# simple.net
KiCad netlist of a schematic drawn in EAGLE
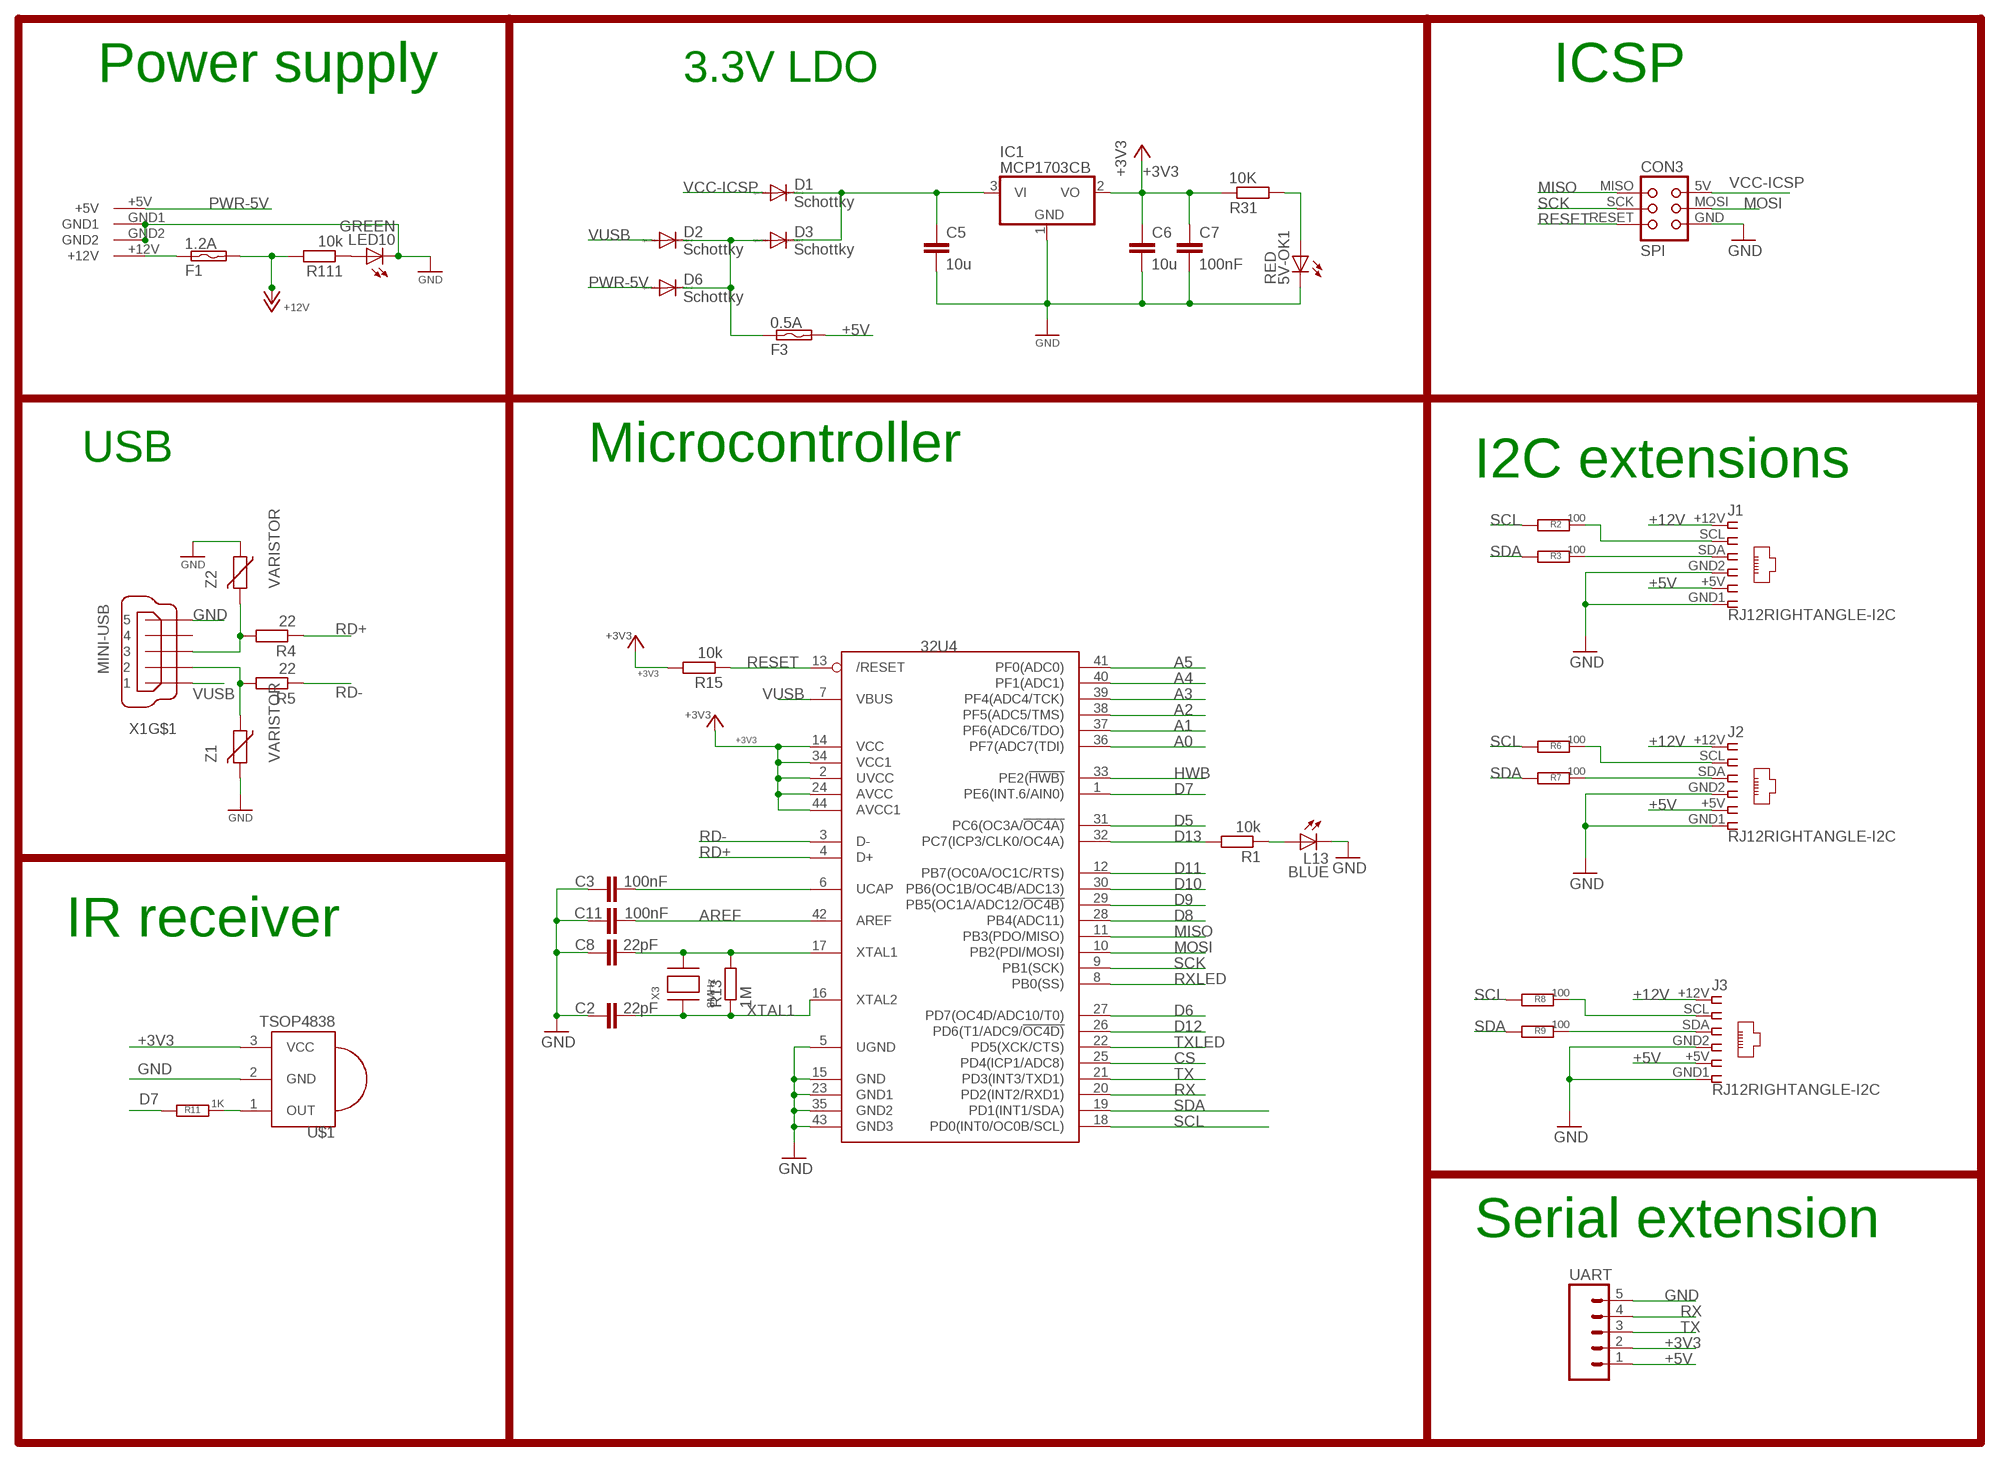
[diagram p0: schematic, sheet 1]

(export (version "E")
  (design (tool "Eeschema 10.0.6"))
  (components
    (comp (ref "5V-OK1")
      (value "RED")
      (footprint "eagle-import:CHIP-LED0805")
      (libsource (lib "eagle-import") (part "LEDCHIP-LED0805"))
    )
    (comp (ref "C2")
      (value "22pF")
      (footprint "eagle-import:C0805K")
      (libsource (lib "eagle-import") (part "C-EUC0805K"))
    )
    (comp (ref "C3")
      (value "100nF")
      (footprint "eagle-import:C0805K")
      (libsource (lib "eagle-import") (part "C-EUC0805K"))
    )
    (comp (ref "C5")
      (value "10u")
      (footprint "eagle-import:C0805K")
      (fields (field (name "MPN") "77-VJ1206V106ZXQTBC"))
      (libsource (lib "eagle-import") (part "rcl_334_C-EUC0805K"))
    )
    (comp (ref "C6")
      (value "10u")
      (footprint "eagle-import:C0805K")
      (fields (field (name "MPN") "77-VJ1206V106ZXQTBC"))
      (libsource (lib "eagle-import") (part "rcl_334_C-EUC0805K"))
    )
    (comp (ref "C7")
      (value "100nF")
      (footprint "eagle-import:C0805K")
      (fields (field (name "MPN") "80-C1206C104K5R"))
      (libsource (lib "eagle-import") (part "rcl_334_C-EUC0805K"))
    )
    (comp (ref "C8")
      (value "22pF")
      (footprint "eagle-import:C0805K")
      (libsource (lib "eagle-import") (part "C-EUC0805K"))
    )
    (comp (ref "C11")
      (value "100nF")
      (footprint "eagle-import:C0805K")
      (libsource (lib "eagle-import") (part "C-EUC0805K"))
    )
    (comp (ref "CON3")
      (value "SPI")
      (footprint "eagle-import:TC2030-MCP-NL")
      (libsource (lib "eagle-import") (part "TINYISPT"))
    )
    (comp (ref "D1")
      (value "Schottky")
      (footprint "eagle-import:SOD123")
      (fields (field (name "MPN") "621-1N5819HW-F"))
      (libsource (lib "eagle-import") (part "MBR0520LT"))
    )
    (comp (ref "D2")
      (value "Schottky")
      (footprint "eagle-import:SOD123")
      (fields (field (name "MPN") "621-1N5819HW-F"))
      (libsource (lib "eagle-import") (part "MBR0520LT"))
    )
    (comp (ref "D3")
      (value "Schottky")
      (footprint "eagle-import:SOD123")
      (fields (field (name "MPN") "621-1N5819HW-F"))
      (libsource (lib "eagle-import") (part "MBR0520LT"))
    )
    (comp (ref "D6")
      (value "Schottky")
      (footprint "eagle-import:SOD123")
      (fields (field (name "MPN") "621-1N5819HW-F"))
      (libsource (lib "eagle-import") (part "MBR0520LT"))
    )
    (comp (ref "F1")
      (value "1.2A")
      (footprint "eagle-import:C1812")
      (libsource (lib "eagle-import") (part "POLYSWITCHSMD1812"))
    )
    (comp (ref "F3")
      (value "0.5A")
      (footprint "eagle-import:C1812")
      (libsource (lib "eagle-import") (part "POLYSWITCHSMD1812"))
    )
    (comp (ref "IC1")
      (value "MCP1703CB")
      (footprint "eagle-import:SOT23")
      (libsource (lib "eagle-import") (part "MCP1703CB"))
    )
    (comp (ref "J1")
      (value "RJ12RIGHTANGLE-I2C")
      (footprint "eagle-import:RJ12-RIGHTANGLE-I2C")
      (libsource (lib "eagle-import") (part "RJ12RIGHTANGLE-I2C"))
    )
    (comp (ref "J2")
      (value "RJ12RIGHTANGLE-I2C")
      (footprint "eagle-import:RJ12-RIGHTANGLE-I2C")
      (libsource (lib "eagle-import") (part "RJ12RIGHTANGLE-I2C"))
    )
    (comp (ref "J3")
      (value "RJ12RIGHTANGLE-I2C")
      (footprint "eagle-import:RJ12-RIGHTANGLE-I2C")
      (libsource (lib "eagle-import") (part "RJ12RIGHTANGLE-I2C"))
    )
    (comp (ref "L13")
      (value "BLUE")
      (footprint "eagle-import:CHIP-LED0805")
      (libsource (lib "eagle-import") (part "LEDCHIP-LED0805"))
    )
    (comp (ref "LED10")
      (value "GREEN")
      (footprint "eagle-import:CHIP-LED0805")
      (libsource (lib "eagle-import") (part "LEDCHIP-LED0805"))
    )
    (comp (ref "R1")
      (value "10k")
      (footprint "eagle-import:M0805")
      (libsource (lib "eagle-import") (part "resistor_348_R-EU_M0805"))
    )
    (comp (ref "R2")
      (value "100")
      (footprint "eagle-import:R0805")
      (libsource (lib "eagle-import") (part "resistor_348_R-EU_R0805"))
    )
    (comp (ref "R3")
      (value "100")
      (footprint "eagle-import:R0805")
      (libsource (lib "eagle-import") (part "resistor_348_R-EU_R0805"))
    )
    (comp (ref "R4")
      (value "22")
      (footprint "eagle-import:R0805")
      (libsource (lib "eagle-import") (part "R-EU_R0805"))
    )
    (comp (ref "R5")
      (value "22")
      (footprint "eagle-import:R0805")
      (libsource (lib "eagle-import") (part "rcl_334_R-EU_R0805"))
    )
    (comp (ref "R6")
      (value "100")
      (footprint "eagle-import:R0805")
      (libsource (lib "eagle-import") (part "resistor_348_R-EU_R0805"))
    )
    (comp (ref "R7")
      (value "100")
      (footprint "eagle-import:R0805")
      (libsource (lib "eagle-import") (part "resistor_348_R-EU_R0805"))
    )
    (comp (ref "R8")
      (value "100")
      (footprint "eagle-import:R0805")
      (libsource (lib "eagle-import") (part "resistor_348_R-EU_R0805"))
    )
    (comp (ref "R9")
      (value "100")
      (footprint "eagle-import:R0805")
      (libsource (lib "eagle-import") (part "resistor_348_R-EU_R0805"))
    )
    (comp (ref "R11")
      (value "1K")
      (footprint "eagle-import:R0805")
      (libsource (lib "eagle-import") (part "resistor_348_R-EU_R0805"))
    )
    (comp (ref "R13")
      (value "1M")
      (footprint "eagle-import:M0805")
      (libsource (lib "eagle-import") (part "R-EU_M0805"))
    )
    (comp (ref "R15")
      (value "10k")
      (footprint "eagle-import:M0805")
      (libsource (lib "eagle-import") (part "resistor_348_R-EU_M0805"))
    )
    (comp (ref "R31")
      (value "10K")
      (footprint "eagle-import:R0805")
      (libsource (lib "eagle-import") (part "resistor_348_R-EU_R0805"))
    )
    (comp (ref "R111")
      (value "10k")
      (footprint "eagle-import:R0805")
      (libsource (lib "eagle-import") (part "R-EU_R0805"))
    )
    (comp (ref "U$1")
      (value "TSOP4838")
      (footprint "eagle-import:PNA460XM")
      (libsource (lib "eagle-import") (part "PNA460XM"))
    )
    (comp (ref "U$4")
      (value "32U4")
      (footprint "eagle-import:TQFP44")
      (libsource (lib "eagle-import") (part "ATMEGA32U4-AU"))
    )
    (comp (ref "U$6")
      (value "KPJX-4S-S")
      (footprint "eagle-import:KPJX-4S-S")
      (libsource (lib "eagle-import") (part "KPJX-4S-S"))
    )
    (comp (ref "UART")
      (value "M05PTH")
      (footprint "eagle-import:1X05")
      (libsource (lib "eagle-import") (part "M05PTH"))
    )
    (comp (ref "X1")
      (value "MINI-USB")
      (footprint "eagle-import:32005-201")
      (fields (field (name "MPN") "649-10033526-N3212LF"))
      (libsource (lib "eagle-import") (part "MINI-USB-SCHIELD-32005-201"))
    )
    (comp (ref "X3")
      (value "8MHz")
      (footprint "eagle-import:NX6035")
      (libsource (lib "eagle-import") (part "XTALNX6035"))
    )
    (comp (ref "Z1")
      (value "VARISTOR")
      (footprint "eagle-import:CT_CN0603")
      (libsource (lib "eagle-import") (part "VARISTORCN0603"))
    )
    (comp (ref "Z2")
      (value "VARISTOR")
      (footprint "eagle-import:CT_CN0603")
      (libsource (lib "eagle-import") (part "VARISTORCN0603"))
    )
  )
  (nets
    (net (code "1") (name "+3V3") (class "Default")
      (node (ref "C6") (pin "1") (pinfunction "1_1") (pintype "passive"))
      (node (ref "C7") (pin "1") (pinfunction "1_1") (pintype "passive"))
      (node (ref "IC1") (pin "2") (pinfunction "VO_2") (pintype "passive"))
      (node (ref "R15") (pin "2") (pinfunction "2_2") (pintype "passive"))
      (node (ref "R31") (pin "1") (pinfunction "1_1") (pintype "passive"))
      (node (ref "U$1") (pin "3") (pinfunction "VCC_3") (pintype "power_in"))
      (node (ref "U$4") (pin "14") (pinfunction "VCC_14") (pintype "bidirectional"))
      (node (ref "U$4") (pin "2") (pinfunction "UVCC_2") (pintype "bidirectional"))
      (node (ref "U$4") (pin "24") (pinfunction "AVCC_24") (pintype "bidirectional"))
      (node (ref "U$4") (pin "34") (pinfunction "VCC1_34") (pintype "bidirectional"))
      (node (ref "U$4") (pin "44") (pinfunction "AVCC1_44") (pintype "bidirectional"))
      (node (ref "UART") (pin "2") (pinfunction "2_2") (pintype "passive"))
    )
    (net (code "2") (name "+12V") (class "Default")
      (node (ref "F1") (pin "2") (pinfunction "2_2") (pintype "passive"))
      (node (ref "J1") (pin "+12V") (pinfunction "1_+12V") (pintype "bidirectional"))
      (node (ref "J2") (pin "+12V") (pinfunction "1_+12V") (pintype "bidirectional"))
      (node (ref "J3") (pin "+12V") (pinfunction "1_+12V") (pintype "bidirectional"))
      (node (ref "R111") (pin "2") (pinfunction "2_2") (pintype "passive"))
    )
    (net (code "3") (name "/+5V") (class "Default")
      (node (ref "F3") (pin "2") (pinfunction "2_2") (pintype "passive"))
      (node (ref "J1") (pin "+5V") (pinfunction "5_+5V") (pintype "bidirectional"))
      (node (ref "J2") (pin "+5V") (pinfunction "5_+5V") (pintype "bidirectional"))
      (node (ref "J3") (pin "+5V") (pinfunction "5_+5V") (pintype "bidirectional"))
      (node (ref "UART") (pin "1") (pinfunction "1_1") (pintype "passive"))
    )
    (net (code "4") (name "/A0") (class "Default")
      (node (ref "U$4") (pin "36") (pinfunction "PF7(ADC7(TDI)_36") (pintype "bidirectional"))
    )
    (net (code "5") (name "/A1") (class "Default")
      (node (ref "U$4") (pin "37") (pinfunction "PF6(ADC6/TDO)_37") (pintype "bidirectional"))
    )
    (net (code "6") (name "/A2") (class "Default")
      (node (ref "U$4") (pin "38") (pinfunction "PF5(ADC5/TMS)_38") (pintype "bidirectional"))
    )
    (net (code "7") (name "/A3") (class "Default")
      (node (ref "U$4") (pin "39") (pinfunction "PF4(ADC4/TCK)_39") (pintype "bidirectional"))
    )
    (net (code "8") (name "/A4") (class "Default")
      (node (ref "U$4") (pin "40") (pinfunction "PF1(ADC1)_40") (pintype "bidirectional"))
    )
    (net (code "9") (name "/A5") (class "Default")
      (node (ref "U$4") (pin "41") (pinfunction "PF0(ADC0)_41") (pintype "bidirectional"))
    )
    (net (code "10") (name "/AREF") (class "Default")
      (node (ref "C11") (pin "1") (pinfunction "1_1") (pintype "passive"))
      (node (ref "U$4") (pin "42") (pinfunction "AREF_42") (pintype "bidirectional"))
    )
    (net (code "11") (name "/CS") (class "Default")
      (node (ref "U$4") (pin "25") (pinfunction "PD4(ICP1/ADC8)_25") (pintype "bidirectional"))
    )
    (net (code "12") (name "/D5") (class "Default")
      (node (ref "U$4") (pin "31") (pinfunction "PC6(OC3A/~{OC4A})_31") (pintype "bidirectional"))
    )
    (net (code "13") (name "/D6") (class "Default")
      (node (ref "U$4") (pin "27") (pinfunction "PD7(OC4D/ADC10/T0)_27") (pintype "bidirectional"))
    )
    (net (code "14") (name "/D7") (class "Default")
      (node (ref "R11") (pin "2") (pinfunction "2_2") (pintype "passive"))
      (node (ref "U$4") (pin "1") (pinfunction "PE6(INT.6/AIN0)_1") (pintype "bidirectional"))
    )
    (net (code "15") (name "/D8") (class "Default")
      (node (ref "U$4") (pin "28") (pinfunction "PB4(ADC11)_28") (pintype "bidirectional"))
    )
    (net (code "16") (name "/D9") (class "Default")
      (node (ref "U$4") (pin "29") (pinfunction "PB5(OC1A/ADC12/~{OC4B})_29") (pintype "bidirectional"))
    )
    (net (code "17") (name "/D10") (class "Default")
      (node (ref "U$4") (pin "30") (pinfunction "PB6(OC1B/OC4B/ADC13)_30") (pintype "bidirectional"))
    )
    (net (code "18") (name "/D11") (class "Default")
      (node (ref "U$4") (pin "12") (pinfunction "PB7(OC0A/OC1C/RTS)_12") (pintype "bidirectional"))
    )
    (net (code "19") (name "/D12") (class "Default")
      (node (ref "U$4") (pin "26") (pinfunction "PD6(T1/ADC9/~{OC4D})_26") (pintype "bidirectional"))
    )
    (net (code "20") (name "/D13") (class "Default")
      (node (ref "R1") (pin "2") (pinfunction "2_2") (pintype "passive"))
      (node (ref "U$4") (pin "32") (pinfunction "PC7(ICP3/CLK0/OC4A)_32") (pintype "bidirectional"))
    )
    (net (code "21") (name "/HWB") (class "Default")
      (node (ref "U$4") (pin "33") (pinfunction "PE2(~{HWB})_33") (pintype "bidirectional"))
    )
    (net (code "22") (name "/MISO") (class "Default")
      (node (ref "CON3") (pin "MISO") (pinfunction "MISO_MISO") (pintype "passive"))
      (node (ref "U$4") (pin "11") (pinfunction "PB3(PDO/MISO)_11") (pintype "bidirectional"))
    )
    (net (code "23") (name "/MOSI") (class "Default")
      (node (ref "CON3") (pin "MOSI") (pinfunction "MOSI_MOSI") (pintype "passive"))
      (node (ref "U$4") (pin "10") (pinfunction "PB2(PDI/MOSI)_10") (pintype "bidirectional"))
    )
    (net (code "24") (name "/PWR-5V") (class "Default")
      (node (ref "D6") (pin "A") (pinfunction "A_A") (pintype "passive"))
      (node (ref "U$6") (pin "+5V") (pinfunction "+5V_+5V") (pintype "power_in"))
    )
    (net (code "25") (name "/RD+") (class "Default")
      (node (ref "R4") (pin "1") (pinfunction "1_1") (pintype "passive"))
      (node (ref "U$4") (pin "4") (pinfunction "D+_4") (pintype "bidirectional"))
    )
    (net (code "26") (name "/RD-") (class "Default")
      (node (ref "R5") (pin "1") (pinfunction "1_1") (pintype "passive"))
      (node (ref "U$4") (pin "3") (pinfunction "D-_3") (pintype "bidirectional"))
    )
    (net (code "27") (name "/RESET") (class "Default")
      (node (ref "CON3") (pin "RESET") (pinfunction "RESET_RESET") (pintype "passive"))
      (node (ref "R15") (pin "1") (pinfunction "1_1") (pintype "passive"))
      (node (ref "U$4") (pin "13") (pinfunction "/RESET_13") (pintype "bidirectional"))
    )
    (net (code "28") (name "/RX") (class "Default")
      (node (ref "U$4") (pin "20") (pinfunction "PD2(INT2/RXD1)_20") (pintype "bidirectional"))
      (node (ref "UART") (pin "4") (pinfunction "4_4") (pintype "passive"))
    )
    (net (code "29") (name "/RXLED") (class "Default")
      (node (ref "U$4") (pin "8") (pinfunction "PB0(SS)_8") (pintype "bidirectional"))
    )
    (net (code "30") (name "/SCK") (class "Default")
      (node (ref "CON3") (pin "SCK") (pinfunction "SCK_SCK") (pintype "passive"))
      (node (ref "U$4") (pin "9") (pinfunction "PB1(SCK)_9") (pintype "bidirectional"))
    )
    (net (code "31") (name "/SCL") (class "Default")
      (node (ref "R2") (pin "2") (pinfunction "2_2") (pintype "passive"))
      (node (ref "R6") (pin "2") (pinfunction "2_2") (pintype "passive"))
      (node (ref "R8") (pin "2") (pinfunction "2_2") (pintype "passive"))
      (node (ref "U$4") (pin "18") (pinfunction "PD0(INT0/OC0B/SCL)_18") (pintype "bidirectional"))
    )
    (net (code "32") (name "/SDA") (class "Default")
      (node (ref "R3") (pin "2") (pinfunction "2_2") (pintype "passive"))
      (node (ref "R7") (pin "2") (pinfunction "2_2") (pintype "passive"))
      (node (ref "R9") (pin "2") (pinfunction "2_2") (pintype "passive"))
      (node (ref "U$4") (pin "19") (pinfunction "PD1(INT1/SDA)_19") (pintype "bidirectional"))
    )
    (net (code "33") (name "/TX") (class "Default")
      (node (ref "U$4") (pin "21") (pinfunction "PD3(INT3/TXD1)_21") (pintype "bidirectional"))
      (node (ref "UART") (pin "3") (pinfunction "3_3") (pintype "passive"))
    )
    (net (code "34") (name "/TXLED") (class "Default")
      (node (ref "U$4") (pin "22") (pinfunction "PD5(XCK/CTS)_22") (pintype "bidirectional"))
    )
    (net (code "35") (name "/VCC-ICSP") (class "Default")
      (node (ref "CON3") (pin "5V") (pinfunction "VCC_5V") (pintype "passive"))
      (node (ref "D1") (pin "A") (pinfunction "A_A") (pintype "passive"))
    )
    (net (code "36") (name "/VUSB") (class "Default")
      (node (ref "D2") (pin "A") (pinfunction "A_A") (pintype "passive"))
      (node (ref "U$4") (pin "7") (pinfunction "VBUS_7") (pintype "bidirectional"))
      (node (ref "X1") (pin "1") (pinfunction "1_1") (pintype "passive"))
    )
    (net (code "37") (name "/XTAL1") (class "Default")
      (node (ref "C2") (pin "2") (pinfunction "2_2") (pintype "passive"))
      (node (ref "R13") (pin "1") (pinfunction "1_1") (pintype "passive"))
      (node (ref "U$4") (pin "16") (pinfunction "XTAL2_16") (pintype "bidirectional"))
      (node (ref "X3") (pin "P$1") (pinfunction "P$1_P$1") (pintype "bidirectional"))
    )
    (net (code "38") (name "GND") (class "Default")
      (node (ref "5V-OK1") (pin "C") (pinfunction "C_C") (pintype "passive"))
      (node (ref "C11") (pin "2") (pinfunction "2_2") (pintype "passive"))
      (node (ref "C2") (pin "1") (pinfunction "1_1") (pintype "passive"))
      (node (ref "C3") (pin "1") (pinfunction "1_1") (pintype "passive"))
      (node (ref "C5") (pin "2") (pinfunction "2_2") (pintype "passive"))
      (node (ref "C6") (pin "2") (pinfunction "2_2") (pintype "passive"))
      (node (ref "C7") (pin "2") (pinfunction "2_2") (pintype "passive"))
      (node (ref "C8") (pin "1") (pinfunction "1_1") (pintype "passive"))
      (node (ref "CON3") (pin "GND") (pinfunction "GND_GND") (pintype "passive"))
      (node (ref "IC1") (pin "1") (pinfunction "GND_1") (pintype "passive"))
      (node (ref "J1") (pin "GND1") (pinfunction "6_GND1") (pintype "bidirectional"))
      (node (ref "J1") (pin "GND2") (pinfunction "4_GND2") (pintype "bidirectional"))
      (node (ref "J2") (pin "GND1") (pinfunction "6_GND1") (pintype "bidirectional"))
      (node (ref "J2") (pin "GND2") (pinfunction "4_GND2") (pintype "bidirectional"))
      (node (ref "J3") (pin "GND1") (pinfunction "6_GND1") (pintype "bidirectional"))
      (node (ref "J3") (pin "GND2") (pinfunction "4_GND2") (pintype "bidirectional"))
      (node (ref "L13") (pin "C") (pinfunction "C_C") (pintype "passive"))
      (node (ref "LED10") (pin "C") (pinfunction "C_C") (pintype "passive"))
      (node (ref "U$1") (pin "2") (pinfunction "GND_2") (pintype "power_in"))
      (node (ref "U$4") (pin "15") (pinfunction "GND_15") (pintype "bidirectional"))
      (node (ref "U$4") (pin "23") (pinfunction "GND1_23") (pintype "bidirectional"))
      (node (ref "U$4") (pin "35") (pinfunction "GND2_35") (pintype "bidirectional"))
      (node (ref "U$4") (pin "43") (pinfunction "GND3_43") (pintype "bidirectional"))
      (node (ref "U$4") (pin "5") (pinfunction "UGND_5") (pintype "bidirectional"))
      (node (ref "U$6") (pin "GND1") (pinfunction "GND1_GND1") (pintype "input"))
      (node (ref "U$6") (pin "GND2") (pinfunction "GND2_GND2") (pintype "input"))
      (node (ref "UART") (pin "5") (pinfunction "5_5") (pintype "passive"))
      (node (ref "X1") (pin "5") (pinfunction "5_5") (pintype "passive"))
      (node (ref "Z1") (pin "2") (pinfunction "2_2") (pintype "passive"))
      (node (ref "Z2") (pin "1") (pinfunction "1_1") (pintype "passive"))
    )
    (net (code "39") (name "Net-(5V-OK1-PadA)") (class "Default")
      (node (ref "5V-OK1") (pin "A") (pinfunction "A_A") (pintype "passive"))
      (node (ref "R31") (pin "2") (pinfunction "2_2") (pintype "passive"))
    )
    (net (code "40") (name "Net-(D2-PadC)") (class "Default")
      (node (ref "D2") (pin "C") (pinfunction "C_C") (pintype "passive"))
      (node (ref "D3") (pin "A") (pinfunction "A_A") (pintype "passive"))
      (node (ref "D6") (pin "C") (pinfunction "C_C") (pintype "passive"))
      (node (ref "F3") (pin "1") (pinfunction "1_1") (pintype "passive"))
    )
    (net (code "41") (name "Net-(F1-Pad1)") (class "Default")
      (node (ref "F1") (pin "1") (pinfunction "1_1") (pintype "passive"))
      (node (ref "U$6") (pin "+12V") (pinfunction "+12V_+12V") (pintype "power_in"))
    )
    (net (code "42") (name "Net-(IC1-VI)") (class "Default")
      (node (ref "C5") (pin "1") (pinfunction "1_1") (pintype "passive"))
      (node (ref "D1") (pin "C") (pinfunction "C_C") (pintype "passive"))
      (node (ref "D3") (pin "C") (pinfunction "C_C") (pintype "passive"))
      (node (ref "IC1") (pin "3") (pinfunction "VI_3") (pintype "input"))
    )
    (net (code "43") (name "Net-(J1-2)") (class "Default")
      (node (ref "J1") (pin "SCL") (pinfunction "2_SCL") (pintype "bidirectional"))
      (node (ref "R2") (pin "1") (pinfunction "1_1") (pintype "passive"))
    )
    (net (code "44") (name "Net-(J1-3)") (class "Default")
      (node (ref "J1") (pin "SDA") (pinfunction "3_SDA") (pintype "bidirectional"))
      (node (ref "R3") (pin "1") (pinfunction "1_1") (pintype "passive"))
    )
    (net (code "45") (name "Net-(J2-2)") (class "Default")
      (node (ref "J2") (pin "SCL") (pinfunction "2_SCL") (pintype "bidirectional"))
      (node (ref "R6") (pin "1") (pinfunction "1_1") (pintype "passive"))
    )
    (net (code "46") (name "Net-(J2-3)") (class "Default")
      (node (ref "J2") (pin "SDA") (pinfunction "3_SDA") (pintype "bidirectional"))
      (node (ref "R7") (pin "1") (pinfunction "1_1") (pintype "passive"))
    )
    (net (code "47") (name "Net-(J3-2)") (class "Default")
      (node (ref "J3") (pin "SCL") (pinfunction "2_SCL") (pintype "bidirectional"))
      (node (ref "R8") (pin "1") (pinfunction "1_1") (pintype "passive"))
    )
    (net (code "48") (name "Net-(J3-3)") (class "Default")
      (node (ref "J3") (pin "SDA") (pinfunction "3_SDA") (pintype "bidirectional"))
      (node (ref "R9") (pin "1") (pinfunction "1_1") (pintype "passive"))
    )
    (net (code "49") (name "Net-(L13-PadA)") (class "Default")
      (node (ref "L13") (pin "A") (pinfunction "A_A") (pintype "passive"))
      (node (ref "R1") (pin "1") (pinfunction "1_1") (pintype "passive"))
    )
    (net (code "50") (name "Net-(LED10-PadA)") (class "Default")
      (node (ref "LED10") (pin "A") (pinfunction "A_A") (pintype "passive"))
      (node (ref "R111") (pin "1") (pinfunction "1_1") (pintype "passive"))
    )
    (net (code "51") (name "Net-(R4-Pad2)") (class "Default")
      (node (ref "R4") (pin "2") (pinfunction "2_2") (pintype "passive"))
      (node (ref "X1") (pin "3") (pinfunction "3_3") (pintype "passive"))
      (node (ref "Z2") (pin "2") (pinfunction "2_2") (pintype "passive"))
    )
    (net (code "52") (name "Net-(R5-Pad2)") (class "Default")
      (node (ref "R5") (pin "2") (pinfunction "2_2") (pintype "passive"))
      (node (ref "X1") (pin "2") (pinfunction "2_2") (pintype "passive"))
      (node (ref "Z1") (pin "1") (pinfunction "1_1") (pintype "passive"))
    )
    (net (code "53") (name "Net-(U$1-OUT)") (class "Default")
      (node (ref "R11") (pin "1") (pinfunction "1_1") (pintype "passive"))
      (node (ref "U$1") (pin "1") (pinfunction "OUT_1") (pintype "output"))
    )
    (net (code "54") (name "Net-(U$4-UCAP)") (class "Default")
      (node (ref "C3") (pin "2") (pinfunction "2_2") (pintype "passive"))
      (node (ref "U$4") (pin "6") (pinfunction "UCAP_6") (pintype "bidirectional"))
    )
    (net (code "55") (name "Net-(U$4-XTAL1)") (class "Default")
      (node (ref "C8") (pin "2") (pinfunction "2_2") (pintype "passive"))
      (node (ref "R13") (pin "2") (pinfunction "2_2") (pintype "passive"))
      (node (ref "U$4") (pin "17") (pinfunction "XTAL1_17") (pintype "bidirectional"))
      (node (ref "X3") (pin "P$2") (pinfunction "P$2_P$2") (pintype "bidirectional"))
    )
    (net (code "56") (name "unconnected-(X1-Pad4)") (class "Default")
      (node (ref "X1") (pin "4") (pinfunction "4_4") (pintype "passive"))
    )
  )
)
